# 16ch_Servo_Driver_V1_2.net
KiCad netlist of a schematic drawn in EAGLE
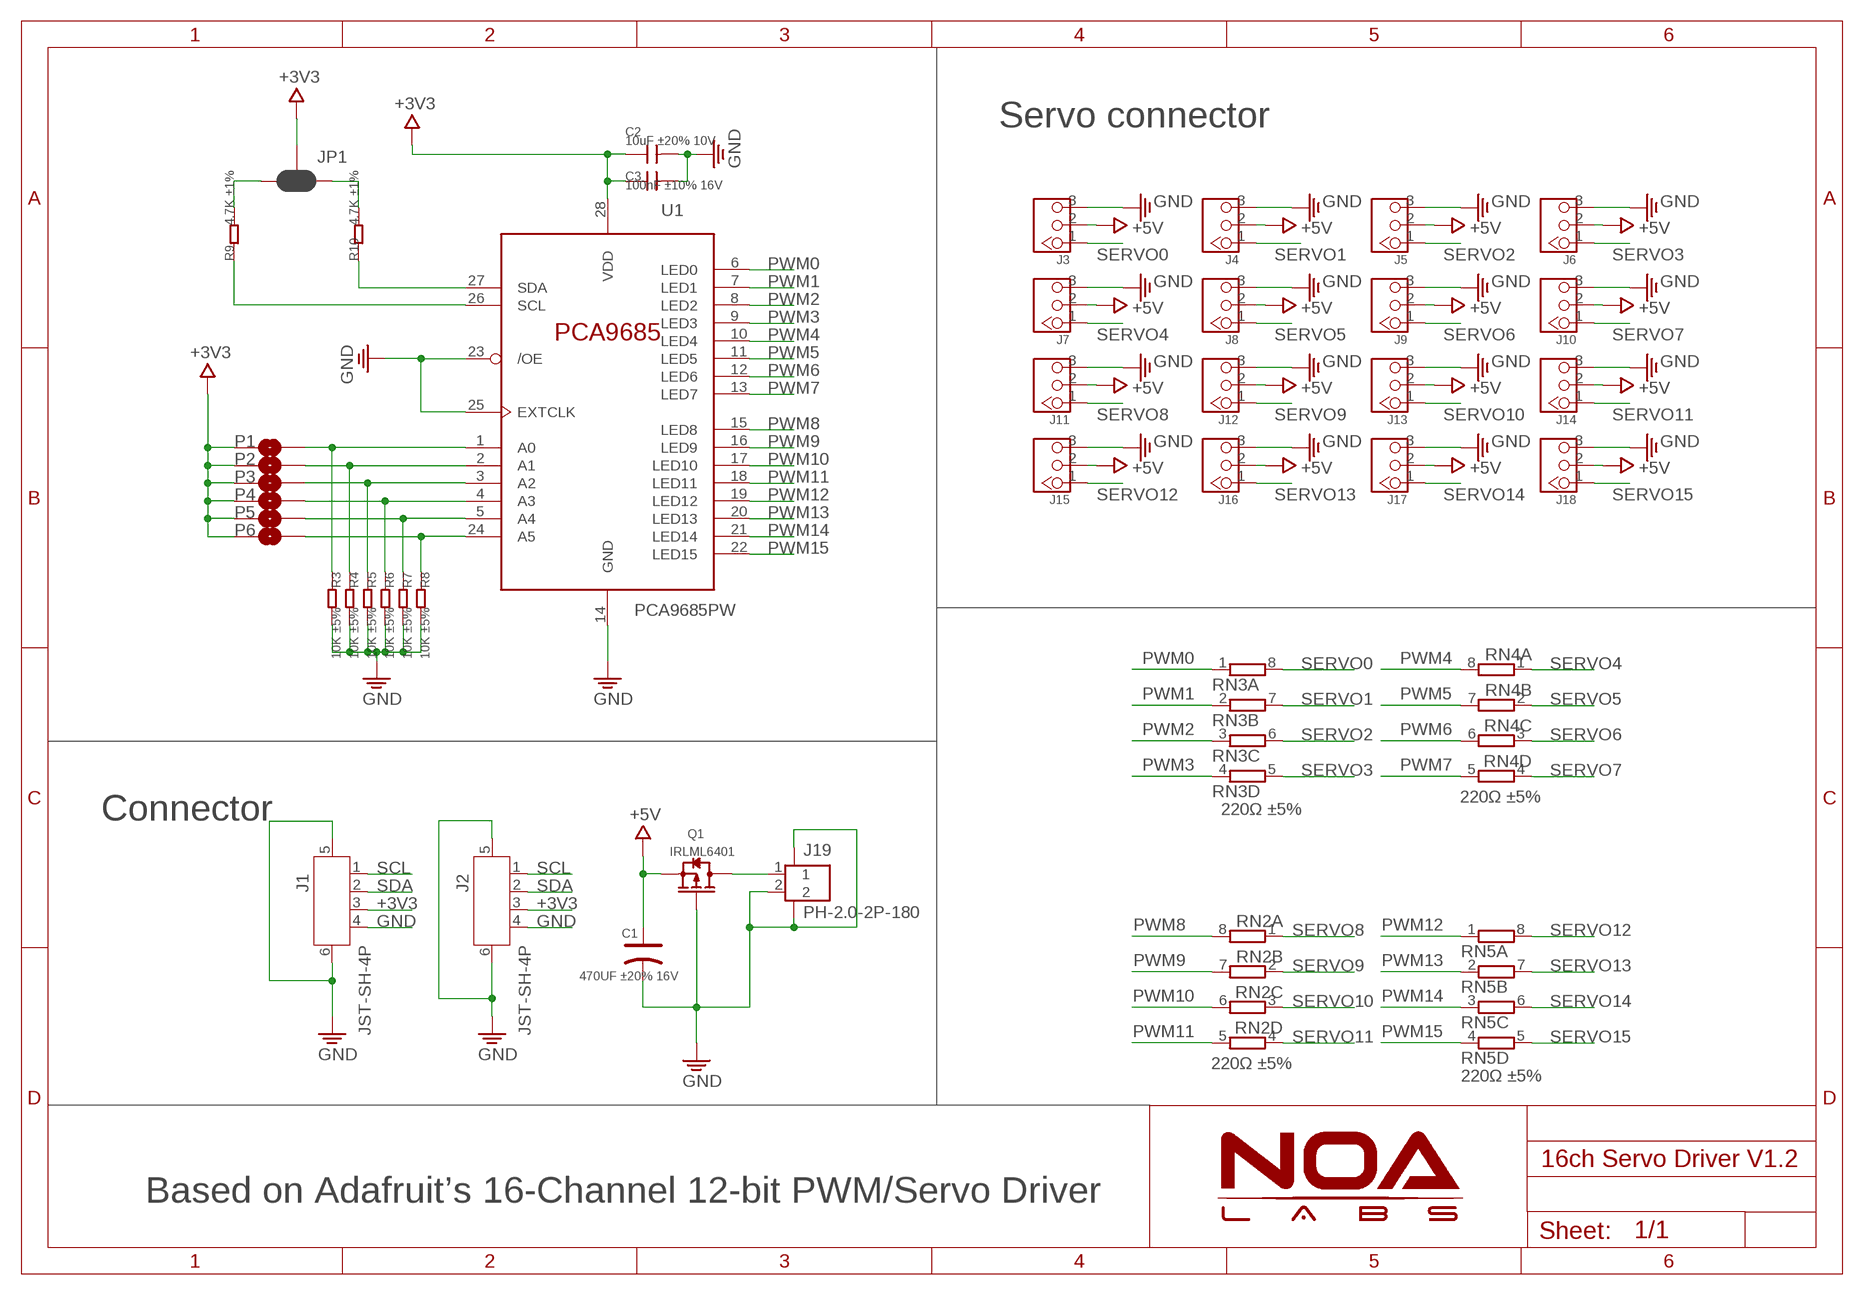
[diagram p0: schematic, sheet 1]

(export (version "E")
  (design (tool "Eeschema 10.0.6"))
  (components
    (comp (ref "C1")
      (value "470UF ±20% 16V")
      (footprint "eagle-import:ELECTRO-SMD-E-7.8MM")
      (libsource (lib "eagle-import") (part "CAP-ELECTRO-E"))
    )
    (comp (ref "C2")
      (value "10uF ±20% 10V")
      (footprint "eagle-import:0402")
      (libsource (lib "eagle-import") (part "C-0402"))
    )
    (comp (ref "C3")
      (value "100nF ±10% 16V")
      (footprint "eagle-import:0402")
      (libsource (lib "eagle-import") (part "C-0402"))
    )
    (comp (ref "J1")
      (value "JST-SH-4P")
      (footprint "eagle-import:JST-SH-4P-90")
      (libsource (lib "eagle-import") (part "JST-SH-4P"))
    )
    (comp (ref "J2")
      (value "JST-SH-4P")
      (footprint "eagle-import:JST-SH-4P-90")
      (libsource (lib "eagle-import") (part "JST-SH-4P"))
    )
    (comp (ref "J3")
      (value "HEADER-3P-2.54")
      (footprint "eagle-import:3P-2.54")
      (libsource (lib "eagle-import") (part "HEADER-3P-2.54"))
    )
    (comp (ref "J4")
      (value "HEADER-3P-2.54")
      (footprint "eagle-import:3P-2.54")
      (libsource (lib "eagle-import") (part "HEADER-3P-2.54"))
    )
    (comp (ref "J5")
      (value "HEADER-3P-2.54")
      (footprint "eagle-import:3P-2.54")
      (libsource (lib "eagle-import") (part "HEADER-3P-2.54"))
    )
    (comp (ref "J6")
      (value "HEADER-3P-2.54")
      (footprint "eagle-import:3P-2.54")
      (libsource (lib "eagle-import") (part "HEADER-3P-2.54"))
    )
    (comp (ref "J7")
      (value "HEADER-3P-2.54")
      (footprint "eagle-import:3P-2.54")
      (libsource (lib "eagle-import") (part "HEADER-3P-2.54"))
    )
    (comp (ref "J8")
      (value "HEADER-3P-2.54")
      (footprint "eagle-import:3P-2.54")
      (libsource (lib "eagle-import") (part "HEADER-3P-2.54"))
    )
    (comp (ref "J9")
      (value "HEADER-3P-2.54")
      (footprint "eagle-import:3P-2.54")
      (libsource (lib "eagle-import") (part "HEADER-3P-2.54"))
    )
    (comp (ref "J10")
      (value "HEADER-3P-2.54")
      (footprint "eagle-import:3P-2.54")
      (libsource (lib "eagle-import") (part "HEADER-3P-2.54"))
    )
    (comp (ref "J11")
      (value "HEADER-3P-2.54")
      (footprint "eagle-import:3P-2.54")
      (libsource (lib "eagle-import") (part "HEADER-3P-2.54"))
    )
    (comp (ref "J12")
      (value "HEADER-3P-2.54")
      (footprint "eagle-import:3P-2.54")
      (libsource (lib "eagle-import") (part "HEADER-3P-2.54"))
    )
    (comp (ref "J13")
      (value "HEADER-3P-2.54")
      (footprint "eagle-import:3P-2.54")
      (libsource (lib "eagle-import") (part "HEADER-3P-2.54"))
    )
    (comp (ref "J14")
      (value "HEADER-3P-2.54")
      (footprint "eagle-import:3P-2.54")
      (libsource (lib "eagle-import") (part "HEADER-3P-2.54"))
    )
    (comp (ref "J15")
      (value "HEADER-3P-2.54")
      (footprint "eagle-import:3P-2.54")
      (libsource (lib "eagle-import") (part "HEADER-3P-2.54"))
    )
    (comp (ref "J16")
      (value "HEADER-3P-2.54")
      (footprint "eagle-import:3P-2.54")
      (libsource (lib "eagle-import") (part "HEADER-3P-2.54"))
    )
    (comp (ref "J17")
      (value "HEADER-3P-2.54")
      (footprint "eagle-import:3P-2.54")
      (libsource (lib "eagle-import") (part "HEADER-3P-2.54"))
    )
    (comp (ref "J18")
      (value "HEADER-3P-2.54")
      (footprint "eagle-import:3P-2.54")
      (libsource (lib "eagle-import") (part "HEADER-3P-2.54"))
    )
    (comp (ref "J19")
      (value "PH-2.0-2P-180")
      (footprint "eagle-import:PH2.0_2P_180")
      (libsource (lib "eagle-import") (part "PH-2.0-2P-180"))
    )
    (comp (ref "JP1")
      (value "JUMPER-SMT_3_2-NC_PASTE_SILK")
      (footprint "eagle-import:SMT-JUMPER_3_2-NC_PASTE_SILK")
      (libsource (lib "eagle-import") (part "JUMPER-SMT_3_2-NC_PASTE_SILK"))
    )
    (comp (ref "P1")
      (value "PAD-SOLDERJUMPERNC")
      (footprint "eagle-import:2P-SMD-3.3X2")
      (libsource (lib "eagle-import") (part "PAD-SOLDERJUMPERNC"))
    )
    (comp (ref "P2")
      (value "PAD-SOLDERJUMPERNC")
      (footprint "eagle-import:2P-SMD-3.3X2")
      (libsource (lib "eagle-import") (part "PAD-SOLDERJUMPERNC"))
    )
    (comp (ref "P3")
      (value "PAD-SOLDERJUMPERNC")
      (footprint "eagle-import:2P-SMD-3.3X2")
      (libsource (lib "eagle-import") (part "PAD-SOLDERJUMPERNC"))
    )
    (comp (ref "P4")
      (value "PAD-SOLDERJUMPERNC")
      (footprint "eagle-import:2P-SMD-3.3X2")
      (libsource (lib "eagle-import") (part "PAD-SOLDERJUMPERNC"))
    )
    (comp (ref "P5")
      (value "PAD-SOLDERJUMPERNC")
      (footprint "eagle-import:2P-SMD-3.3X2")
      (libsource (lib "eagle-import") (part "PAD-SOLDERJUMPERNC"))
    )
    (comp (ref "P6")
      (value "PAD-SOLDERJUMPERNC")
      (footprint "eagle-import:2P-SMD-3.3X2")
      (libsource (lib "eagle-import") (part "PAD-SOLDERJUMPERNC"))
    )
    (comp (ref "Q1")
      (value "IRLML6401")
      (footprint "eagle-import:SOT23")
      (libsource (lib "eagle-import") (part "MOSFET-P-SOT23"))
    )
    (comp (ref "R3")
      (value "10K ±5%")
      (footprint "eagle-import:0402")
      (libsource (lib "eagle-import") (part "R-0402"))
    )
    (comp (ref "R4")
      (value "10K ±5%")
      (footprint "eagle-import:0402")
      (libsource (lib "eagle-import") (part "R-0402"))
    )
    (comp (ref "R5")
      (value "10K ±5%")
      (footprint "eagle-import:0402")
      (libsource (lib "eagle-import") (part "R-0402"))
    )
    (comp (ref "R6")
      (value "10K ±5%")
      (footprint "eagle-import:0402")
      (libsource (lib "eagle-import") (part "R-0402"))
    )
    (comp (ref "R7")
      (value "10K ±5%")
      (footprint "eagle-import:0402")
      (libsource (lib "eagle-import") (part "R-0402"))
    )
    (comp (ref "R8")
      (value "10K ±5%")
      (footprint "eagle-import:0402")
      (libsource (lib "eagle-import") (part "R-0402"))
    )
    (comp (ref "R9")
      (value "4.7K ±1%")
      (footprint "eagle-import:0402")
      (libsource (lib "eagle-import") (part "Discretex_R-0402"))
    )
    (comp (ref "R10")
      (value "4.7K ±1%")
      (footprint "eagle-import:0402")
      (libsource (lib "eagle-import") (part "Discretex_R-0402"))
    )
    (comp (ref "RN2")
      (value "220Ω ±5%")
      (footprint "eagle-import:RESISTOR-DIL_0603-ARC")
      (libsource (lib "eagle-import") (part "RESISTOR-DIL_4R-N0603-ARC"))
    )
    (comp (ref "RN3")
      (value "220Ω ±5%")
      (footprint "eagle-import:RESISTOR-DIL_0603-ARC")
      (libsource (lib "eagle-import") (part "RESISTOR-DIL_4R-N0603-ARC"))
    )
    (comp (ref "RN4")
      (value "220Ω ±5%")
      (footprint "eagle-import:RESISTOR-DIL_0603-ARC")
      (libsource (lib "eagle-import") (part "RESISTOR-DIL_4R-N0603-ARC"))
    )
    (comp (ref "RN5")
      (value "220Ω ±5%")
      (footprint "eagle-import:RESISTOR-DIL_0603-ARC")
      (libsource (lib "eagle-import") (part "RESISTOR-DIL_4R-N0603-ARC"))
    )
    (comp (ref "U1")
      (value "PCA9685PW")
      (footprint "eagle-import:TSSOP28")
      (libsource (lib "eagle-import") (part "PCA9685PW"))
    )
  )
  (nets
    (net (code "1") (name "+3V3") (class "Default")
      (node (ref "C2") (pin "1") (pinfunction "1_1") (pintype "passive"))
      (node (ref "C3") (pin "1") (pinfunction "1_1") (pintype "passive"))
      (node (ref "J1") (pin "3") (pinfunction "3_3") (pintype "bidirectional"))
      (node (ref "J2") (pin "3") (pinfunction "3_3") (pintype "bidirectional"))
      (node (ref "JP1") (pin "2") (pinfunction "2_2") (pintype "passive"))
      (node (ref "P1") (pin "1") (pinfunction "1_1") (pintype "passive"))
      (node (ref "P2") (pin "1") (pinfunction "1_1") (pintype "passive"))
      (node (ref "P3") (pin "1") (pinfunction "1_1") (pintype "passive"))
      (node (ref "P4") (pin "1") (pinfunction "1_1") (pintype "passive"))
      (node (ref "P5") (pin "1") (pinfunction "1_1") (pintype "passive"))
      (node (ref "P6") (pin "1") (pinfunction "1_1") (pintype "passive"))
      (node (ref "U1") (pin "28") (pinfunction "VDD_28") (pintype "power_in"))
    )
    (net (code "2") (name "+5V") (class "Default")
      (node (ref "C1") (pin "+") (pinfunction "+_+") (pintype "passive"))
      (node (ref "J10") (pin "2") (pinfunction "P$2_2") (pintype "bidirectional"))
      (node (ref "J11") (pin "2") (pinfunction "P$2_2") (pintype "bidirectional"))
      (node (ref "J12") (pin "2") (pinfunction "P$2_2") (pintype "bidirectional"))
      (node (ref "J13") (pin "2") (pinfunction "P$2_2") (pintype "bidirectional"))
      (node (ref "J14") (pin "2") (pinfunction "P$2_2") (pintype "bidirectional"))
      (node (ref "J15") (pin "2") (pinfunction "P$2_2") (pintype "bidirectional"))
      (node (ref "J16") (pin "2") (pinfunction "P$2_2") (pintype "bidirectional"))
      (node (ref "J17") (pin "2") (pinfunction "P$2_2") (pintype "bidirectional"))
      (node (ref "J18") (pin "2") (pinfunction "P$2_2") (pintype "bidirectional"))
      (node (ref "J3") (pin "2") (pinfunction "P$2_2") (pintype "bidirectional"))
      (node (ref "J4") (pin "2") (pinfunction "P$2_2") (pintype "bidirectional"))
      (node (ref "J5") (pin "2") (pinfunction "P$2_2") (pintype "bidirectional"))
      (node (ref "J6") (pin "2") (pinfunction "P$2_2") (pintype "bidirectional"))
      (node (ref "J7") (pin "2") (pinfunction "P$2_2") (pintype "bidirectional"))
      (node (ref "J8") (pin "2") (pinfunction "P$2_2") (pintype "bidirectional"))
      (node (ref "J9") (pin "2") (pinfunction "P$2_2") (pintype "bidirectional"))
      (node (ref "Q1") (pin "2") (pinfunction "S_2") (pintype "passive"))
    )
    (net (code "3") (name "/PWM0") (class "Default")
      (node (ref "RN3") (pin "1") (pinfunction "1_1") (pintype "passive"))
      (node (ref "U1") (pin "6") (pinfunction "LED0_6") (pintype "bidirectional"))
    )
    (net (code "4") (name "/PWM1") (class "Default")
      (node (ref "RN3") (pin "2") (pinfunction "1_2") (pintype "passive"))
      (node (ref "U1") (pin "7") (pinfunction "LED1_7") (pintype "bidirectional"))
    )
    (net (code "5") (name "/PWM2") (class "Default")
      (node (ref "RN3") (pin "3") (pinfunction "1_3") (pintype "passive"))
      (node (ref "U1") (pin "8") (pinfunction "LED2_8") (pintype "bidirectional"))
    )
    (net (code "6") (name "/PWM3") (class "Default")
      (node (ref "RN3") (pin "4") (pinfunction "1_4") (pintype "passive"))
      (node (ref "U1") (pin "9") (pinfunction "LED3_9") (pintype "bidirectional"))
    )
    (net (code "7") (name "/PWM4") (class "Default")
      (node (ref "RN4") (pin "8") (pinfunction "2_8") (pintype "passive"))
      (node (ref "U1") (pin "10") (pinfunction "LED4_10") (pintype "bidirectional"))
    )
    (net (code "8") (name "/PWM5") (class "Default")
      (node (ref "RN4") (pin "7") (pinfunction "2_7") (pintype "passive"))
      (node (ref "U1") (pin "11") (pinfunction "LED5_11") (pintype "bidirectional"))
    )
    (net (code "9") (name "/PWM6") (class "Default")
      (node (ref "RN4") (pin "6") (pinfunction "2_6") (pintype "passive"))
      (node (ref "U1") (pin "12") (pinfunction "LED6_12") (pintype "bidirectional"))
    )
    (net (code "10") (name "/PWM7") (class "Default")
      (node (ref "RN4") (pin "5") (pinfunction "2_5") (pintype "passive"))
      (node (ref "U1") (pin "13") (pinfunction "LED7_13") (pintype "bidirectional"))
    )
    (net (code "11") (name "/PWM8") (class "Default")
      (node (ref "RN2") (pin "8") (pinfunction "2_8") (pintype "passive"))
      (node (ref "U1") (pin "15") (pinfunction "LED8_15") (pintype "bidirectional"))
    )
    (net (code "12") (name "/PWM9") (class "Default")
      (node (ref "RN2") (pin "7") (pinfunction "2_7") (pintype "passive"))
      (node (ref "U1") (pin "16") (pinfunction "LED9_16") (pintype "bidirectional"))
    )
    (net (code "13") (name "/PWM10") (class "Default")
      (node (ref "RN2") (pin "6") (pinfunction "2_6") (pintype "passive"))
      (node (ref "U1") (pin "17") (pinfunction "LED10_17") (pintype "bidirectional"))
    )
    (net (code "14") (name "/PWM11") (class "Default")
      (node (ref "RN2") (pin "5") (pinfunction "2_5") (pintype "passive"))
      (node (ref "U1") (pin "18") (pinfunction "LED11_18") (pintype "bidirectional"))
    )
    (net (code "15") (name "/PWM12") (class "Default")
      (node (ref "RN5") (pin "1") (pinfunction "1_1") (pintype "passive"))
      (node (ref "U1") (pin "19") (pinfunction "LED12_19") (pintype "bidirectional"))
    )
    (net (code "16") (name "/PWM13") (class "Default")
      (node (ref "RN5") (pin "2") (pinfunction "1_2") (pintype "passive"))
      (node (ref "U1") (pin "20") (pinfunction "LED13_20") (pintype "bidirectional"))
    )
    (net (code "17") (name "/PWM14") (class "Default")
      (node (ref "RN5") (pin "3") (pinfunction "1_3") (pintype "passive"))
      (node (ref "U1") (pin "21") (pinfunction "LED14_21") (pintype "bidirectional"))
    )
    (net (code "18") (name "/PWM15") (class "Default")
      (node (ref "RN5") (pin "4") (pinfunction "1_4") (pintype "passive"))
      (node (ref "U1") (pin "22") (pinfunction "LED15_22") (pintype "bidirectional"))
    )
    (net (code "19") (name "/SCL") (class "Default")
      (node (ref "J1") (pin "1") (pinfunction "1_1") (pintype "bidirectional"))
      (node (ref "J2") (pin "1") (pinfunction "1_1") (pintype "bidirectional"))
      (node (ref "R9") (pin "1") (pinfunction "1_1") (pintype "passive"))
      (node (ref "U1") (pin "26") (pinfunction "SCL_26") (pintype "bidirectional"))
    )
    (net (code "20") (name "/SDA") (class "Default")
      (node (ref "J1") (pin "2") (pinfunction "2_2") (pintype "bidirectional"))
      (node (ref "J2") (pin "2") (pinfunction "2_2") (pintype "bidirectional"))
      (node (ref "R10") (pin "1") (pinfunction "1_1") (pintype "passive"))
      (node (ref "U1") (pin "27") (pinfunction "SDA_27") (pintype "bidirectional"))
    )
    (net (code "21") (name "/SERVO0") (class "Default")
      (node (ref "J3") (pin "1") (pinfunction "P$1_1") (pintype "bidirectional"))
      (node (ref "RN3") (pin "8") (pinfunction "2_8") (pintype "passive"))
    )
    (net (code "22") (name "/SERVO1") (class "Default")
      (node (ref "J4") (pin "1") (pinfunction "P$1_1") (pintype "bidirectional"))
      (node (ref "RN3") (pin "7") (pinfunction "2_7") (pintype "passive"))
    )
    (net (code "23") (name "/SERVO2") (class "Default")
      (node (ref "J5") (pin "1") (pinfunction "P$1_1") (pintype "bidirectional"))
      (node (ref "RN3") (pin "6") (pinfunction "2_6") (pintype "passive"))
    )
    (net (code "24") (name "/SERVO3") (class "Default")
      (node (ref "J6") (pin "1") (pinfunction "P$1_1") (pintype "bidirectional"))
      (node (ref "RN3") (pin "5") (pinfunction "2_5") (pintype "passive"))
    )
    (net (code "25") (name "/SERVO4") (class "Default")
      (node (ref "J7") (pin "1") (pinfunction "P$1_1") (pintype "bidirectional"))
      (node (ref "RN4") (pin "1") (pinfunction "1_1") (pintype "passive"))
    )
    (net (code "26") (name "/SERVO5") (class "Default")
      (node (ref "J8") (pin "1") (pinfunction "P$1_1") (pintype "bidirectional"))
      (node (ref "RN4") (pin "2") (pinfunction "1_2") (pintype "passive"))
    )
    (net (code "27") (name "/SERVO6") (class "Default")
      (node (ref "J9") (pin "1") (pinfunction "P$1_1") (pintype "bidirectional"))
      (node (ref "RN4") (pin "3") (pinfunction "1_3") (pintype "passive"))
    )
    (net (code "28") (name "/SERVO7") (class "Default")
      (node (ref "J10") (pin "1") (pinfunction "P$1_1") (pintype "bidirectional"))
      (node (ref "RN4") (pin "4") (pinfunction "1_4") (pintype "passive"))
    )
    (net (code "29") (name "/SERVO8") (class "Default")
      (node (ref "J11") (pin "1") (pinfunction "P$1_1") (pintype "bidirectional"))
      (node (ref "RN2") (pin "1") (pinfunction "1_1") (pintype "passive"))
    )
    (net (code "30") (name "/SERVO9") (class "Default")
      (node (ref "J12") (pin "1") (pinfunction "P$1_1") (pintype "bidirectional"))
      (node (ref "RN2") (pin "2") (pinfunction "1_2") (pintype "passive"))
    )
    (net (code "31") (name "/SERVO10") (class "Default")
      (node (ref "J13") (pin "1") (pinfunction "P$1_1") (pintype "bidirectional"))
      (node (ref "RN2") (pin "3") (pinfunction "1_3") (pintype "passive"))
    )
    (net (code "32") (name "/SERVO11") (class "Default")
      (node (ref "J14") (pin "1") (pinfunction "P$1_1") (pintype "bidirectional"))
      (node (ref "RN2") (pin "4") (pinfunction "1_4") (pintype "passive"))
    )
    (net (code "33") (name "/SERVO12") (class "Default")
      (node (ref "J15") (pin "1") (pinfunction "P$1_1") (pintype "bidirectional"))
      (node (ref "RN5") (pin "8") (pinfunction "2_8") (pintype "passive"))
    )
    (net (code "34") (name "/SERVO13") (class "Default")
      (node (ref "J16") (pin "1") (pinfunction "P$1_1") (pintype "bidirectional"))
      (node (ref "RN5") (pin "7") (pinfunction "2_7") (pintype "passive"))
    )
    (net (code "35") (name "/SERVO14") (class "Default")
      (node (ref "J17") (pin "1") (pinfunction "P$1_1") (pintype "bidirectional"))
      (node (ref "RN5") (pin "6") (pinfunction "2_6") (pintype "passive"))
    )
    (net (code "36") (name "/SERVO15") (class "Default")
      (node (ref "J18") (pin "1") (pinfunction "P$1_1") (pintype "bidirectional"))
      (node (ref "RN5") (pin "5") (pinfunction "2_5") (pintype "passive"))
    )
    (net (code "37") (name "GND") (class "Default")
      (node (ref "C1") (pin "-") (pinfunction "-_-") (pintype "passive"))
      (node (ref "C2") (pin "2") (pinfunction "2_2") (pintype "passive"))
      (node (ref "C3") (pin "2") (pinfunction "2_2") (pintype "passive"))
      (node (ref "J1") (pin "4") (pinfunction "4_4") (pintype "bidirectional"))
      (node (ref "J1") (pin "5") (pinfunction "5_5") (pintype "bidirectional"))
      (node (ref "J1") (pin "6") (pinfunction "6_6") (pintype "bidirectional"))
      (node (ref "J10") (pin "3") (pinfunction "P$3_3") (pintype "bidirectional"))
      (node (ref "J11") (pin "3") (pinfunction "P$3_3") (pintype "bidirectional"))
      (node (ref "J12") (pin "3") (pinfunction "P$3_3") (pintype "bidirectional"))
      (node (ref "J13") (pin "3") (pinfunction "P$3_3") (pintype "bidirectional"))
      (node (ref "J14") (pin "3") (pinfunction "P$3_3") (pintype "bidirectional"))
      (node (ref "J15") (pin "3") (pinfunction "P$3_3") (pintype "bidirectional"))
      (node (ref "J16") (pin "3") (pinfunction "P$3_3") (pintype "bidirectional"))
      (node (ref "J17") (pin "3") (pinfunction "P$3_3") (pintype "bidirectional"))
      (node (ref "J18") (pin "3") (pinfunction "P$3_3") (pintype "bidirectional"))
      (node (ref "J19") (pin "2") (pinfunction "2_2") (pintype "bidirectional"))
      (node (ref "J19") (pin "3") (pinfunction "3_3") (pintype "bidirectional"))
      (node (ref "J19") (pin "4") (pinfunction "4_4") (pintype "bidirectional"))
      (node (ref "J2") (pin "4") (pinfunction "4_4") (pintype "bidirectional"))
      (node (ref "J2") (pin "5") (pinfunction "5_5") (pintype "bidirectional"))
      (node (ref "J2") (pin "6") (pinfunction "6_6") (pintype "bidirectional"))
      (node (ref "J3") (pin "3") (pinfunction "P$3_3") (pintype "bidirectional"))
      (node (ref "J4") (pin "3") (pinfunction "P$3_3") (pintype "bidirectional"))
      (node (ref "J5") (pin "3") (pinfunction "P$3_3") (pintype "bidirectional"))
      (node (ref "J6") (pin "3") (pinfunction "P$3_3") (pintype "bidirectional"))
      (node (ref "J7") (pin "3") (pinfunction "P$3_3") (pintype "bidirectional"))
      (node (ref "J8") (pin "3") (pinfunction "P$3_3") (pintype "bidirectional"))
      (node (ref "J9") (pin "3") (pinfunction "P$3_3") (pintype "bidirectional"))
      (node (ref "Q1") (pin "1") (pinfunction "G_1") (pintype "passive"))
      (node (ref "R3") (pin "2") (pinfunction "2_2") (pintype "passive"))
      (node (ref "R4") (pin "2") (pinfunction "2_2") (pintype "passive"))
      (node (ref "R5") (pin "2") (pinfunction "2_2") (pintype "passive"))
      (node (ref "R6") (pin "2") (pinfunction "2_2") (pintype "passive"))
      (node (ref "R7") (pin "2") (pinfunction "2_2") (pintype "passive"))
      (node (ref "R8") (pin "2") (pinfunction "2_2") (pintype "passive"))
      (node (ref "U1") (pin "14") (pinfunction "GND_14") (pintype "power_in"))
      (node (ref "U1") (pin "23") (pinfunction "/OE_23") (pintype "bidirectional"))
      (node (ref "U1") (pin "25") (pinfunction "EXTCLK_25") (pintype "input"))
    )
    (net (code "38") (name "Net-(JP1-Pad1)") (class "Default")
      (node (ref "JP1") (pin "1") (pinfunction "1_1") (pintype "passive"))
      (node (ref "R10") (pin "2") (pinfunction "2_2") (pintype "passive"))
    )
    (net (code "39") (name "Net-(JP1-Pad3)") (class "Default")
      (node (ref "JP1") (pin "3") (pinfunction "3_3") (pintype "passive"))
      (node (ref "R9") (pin "2") (pinfunction "2_2") (pintype "passive"))
    )
    (net (code "40") (name "Net-(Q1-D)") (class "Default")
      (node (ref "J19") (pin "1") (pinfunction "1_1") (pintype "bidirectional"))
      (node (ref "Q1") (pin "3") (pinfunction "D_3") (pintype "passive"))
    )
    (net (code "41") (name "Net-(U1-A0)") (class "Default")
      (node (ref "P1") (pin "2") (pinfunction "2_2") (pintype "passive"))
      (node (ref "R3") (pin "1") (pinfunction "1_1") (pintype "passive"))
      (node (ref "U1") (pin "1") (pinfunction "A0_1") (pintype "bidirectional"))
    )
    (net (code "42") (name "Net-(U1-A1)") (class "Default")
      (node (ref "P2") (pin "2") (pinfunction "2_2") (pintype "passive"))
      (node (ref "R4") (pin "1") (pinfunction "1_1") (pintype "passive"))
      (node (ref "U1") (pin "2") (pinfunction "A1_2") (pintype "bidirectional"))
    )
    (net (code "43") (name "Net-(U1-A2)") (class "Default")
      (node (ref "P3") (pin "2") (pinfunction "2_2") (pintype "passive"))
      (node (ref "R5") (pin "1") (pinfunction "1_1") (pintype "passive"))
      (node (ref "U1") (pin "3") (pinfunction "A2_3") (pintype "bidirectional"))
    )
    (net (code "44") (name "Net-(U1-A3)") (class "Default")
      (node (ref "P4") (pin "2") (pinfunction "2_2") (pintype "passive"))
      (node (ref "R6") (pin "1") (pinfunction "1_1") (pintype "passive"))
      (node (ref "U1") (pin "4") (pinfunction "A3_4") (pintype "bidirectional"))
    )
    (net (code "45") (name "Net-(U1-A4)") (class "Default")
      (node (ref "P5") (pin "2") (pinfunction "2_2") (pintype "passive"))
      (node (ref "R7") (pin "1") (pinfunction "1_1") (pintype "passive"))
      (node (ref "U1") (pin "5") (pinfunction "A4_5") (pintype "bidirectional"))
    )
    (net (code "46") (name "Net-(U1-A5)") (class "Default")
      (node (ref "P6") (pin "2") (pinfunction "2_2") (pintype "passive"))
      (node (ref "R8") (pin "1") (pinfunction "1_1") (pintype "passive"))
      (node (ref "U1") (pin "24") (pinfunction "A5_24") (pintype "bidirectional"))
    )
  )
)
